# PowerMonitoring.net
KiCad netlist of a schematic drawn in Altium Designer
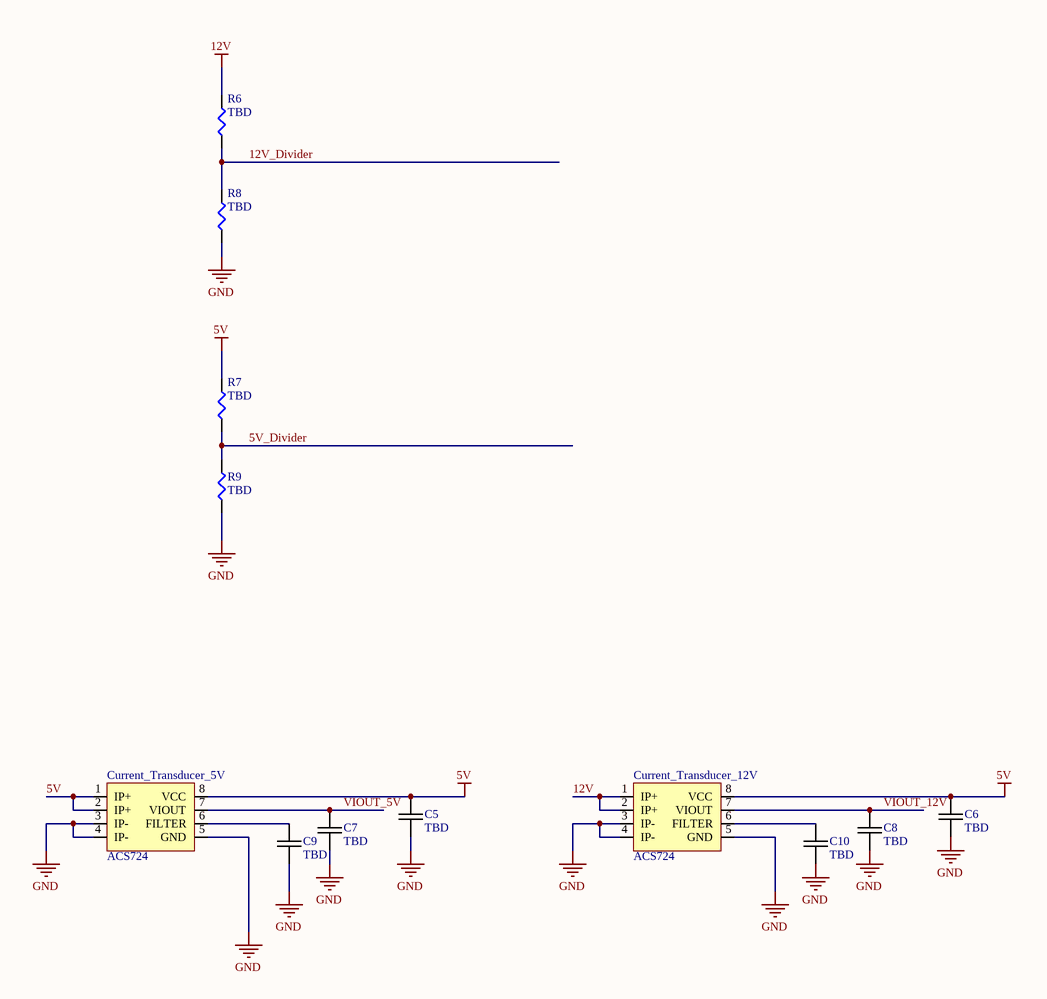
[diagram p0: PowerMonitoring.SchDoc]

(export (version "E")
  (design (tool "Eeschema 10.0.6"))
  (components
    (comp (ref "C5")
      (value "TBD")
      (footprint "0805C-GENERIC")
      (description "CAPACITOR 0805 CERAMIC VALUE TO BE DETERMINED")
      (libsource (lib "MARCS Library Main") (part "0805C-TBD"))
    )
    (comp (ref "C6")
      (value "TBD")
      (footprint "0805C-GENERIC")
      (description "CAPACITOR 0805 CERAMIC VALUE TO BE DETERMINED")
      (libsource (lib "MARCS Library Main") (part "0805C-TBD"))
    )
    (comp (ref "C7")
      (value "TBD")
      (footprint "0805C-GENERIC")
      (description "CAPACITOR 0805 CERAMIC VALUE TO BE DETERMINED")
      (libsource (lib "MARCS Library Main") (part "0805C-TBD"))
    )
    (comp (ref "C8")
      (value "TBD")
      (footprint "0805C-GENERIC")
      (description "CAPACITOR 0805 CERAMIC VALUE TO BE DETERMINED")
      (libsource (lib "MARCS Library Main") (part "0805C-TBD"))
    )
    (comp (ref "C9")
      (value "TBD")
      (footprint "0805C-GENERIC")
      (description "CAPACITOR 0805 CERAMIC VALUE TO BE DETERMINED")
      (libsource (lib "MARCS Library Main") (part "0805C-TBD"))
    )
    (comp (ref "C10")
      (value "TBD")
      (footprint "0805C-GENERIC")
      (description "CAPACITOR 0805 CERAMIC VALUE TO BE DETERMINED")
      (libsource (lib "MARCS Library Main") (part "0805C-TBD"))
    )
    (comp (ref "Current_Transducer_5V")
      (value "ACS724")
      (footprint "SOIC-8 V3")
      (libsource (lib "MARCS Library Main") (part "ACS724"))
    )
    (comp (ref "Current_Transducer_12V")
      (value "ACS724")
      (footprint "SOIC-8 V3")
      (libsource (lib "MARCS Library Main") (part "ACS724"))
    )
    (comp (ref "R6")
      (value "TBD")
      (footprint "0805R-GENERIC")
      (description "RESISTOR 0805 VALUE TO BE DETERMINED")
      (libsource (lib "MARCS Library Main") (part "0805R-TBD"))
    )
    (comp (ref "R7")
      (value "TBD")
      (footprint "0805R-GENERIC")
      (description "RESISTOR 0805 VALUE TO BE DETERMINED")
      (libsource (lib "MARCS Library Main") (part "0805R-TBD"))
    )
    (comp (ref "R8")
      (value "TBD")
      (footprint "0805R-GENERIC")
      (description "RESISTOR 0805 VALUE TO BE DETERMINED")
      (libsource (lib "MARCS Library Main") (part "0805R-TBD"))
    )
    (comp (ref "R9")
      (value "TBD")
      (footprint "0805R-GENERIC")
      (description "RESISTOR 0805 VALUE TO BE DETERMINED")
      (libsource (lib "MARCS Library Main") (part "0805R-TBD"))
    )
  )
  (nets
    (net (code "1") (name "/5V_Divider") (class "Default")
      (node (ref "R7") (pin "1") (pintype "passive"))
      (node (ref "R9") (pin "1") (pintype "passive"))
    )
    (net (code "2") (name "/12V_Divider") (class "Default")
      (node (ref "R6") (pin "1") (pintype "passive"))
      (node (ref "R8") (pin "2") (pintype "passive"))
    )
    (net (code "3") (name "/VIOUT_5V") (class "Default")
      (node (ref "C7") (pin "1") (pintype "passive"))
      (node (ref "Current_Transducer_5V") (pin "7") (pinfunction "VIOUT_7") (pintype "passive"))
    )
    (net (code "4") (name "/VIOUT_12V") (class "Default")
      (node (ref "C8") (pin "1") (pintype "passive"))
      (node (ref "Current_Transducer_12V") (pin "7") (pinfunction "VIOUT_7") (pintype "passive"))
    )
    (net (code "5") (name "5V") (class "Default")
      (node (ref "C5") (pin "1") (pintype "passive"))
      (node (ref "C6") (pin "1") (pintype "passive"))
      (node (ref "Current_Transducer_12V") (pin "8") (pinfunction "VCC_8") (pintype "passive"))
      (node (ref "Current_Transducer_5V") (pin "1") (pinfunction "IP+_1") (pintype "passive"))
      (node (ref "Current_Transducer_5V") (pin "2") (pinfunction "IP+_2") (pintype "passive"))
      (node (ref "Current_Transducer_5V") (pin "8") (pinfunction "VCC_8") (pintype "passive"))
      (node (ref "R7") (pin "2") (pintype "passive"))
    )
    (net (code "6") (name "12V") (class "Default")
      (node (ref "Current_Transducer_12V") (pin "1") (pinfunction "IP+_1") (pintype "passive"))
      (node (ref "Current_Transducer_12V") (pin "2") (pinfunction "IP+_2") (pintype "passive"))
      (node (ref "R6") (pin "2") (pintype "passive"))
    )
    (net (code "7") (name "GND") (class "Default")
      (node (ref "C10") (pin "2") (pintype "passive"))
      (node (ref "C5") (pin "2") (pintype "passive"))
      (node (ref "C6") (pin "2") (pintype "passive"))
      (node (ref "C7") (pin "2") (pintype "passive"))
      (node (ref "C8") (pin "2") (pintype "passive"))
      (node (ref "C9") (pin "2") (pintype "passive"))
      (node (ref "Current_Transducer_12V") (pin "3") (pinfunction "IP-_3") (pintype "passive"))
      (node (ref "Current_Transducer_12V") (pin "4") (pinfunction "IP-_4") (pintype "passive"))
      (node (ref "Current_Transducer_12V") (pin "5") (pinfunction "GND_5") (pintype "passive"))
      (node (ref "Current_Transducer_5V") (pin "3") (pinfunction "IP-_3") (pintype "passive"))
      (node (ref "Current_Transducer_5V") (pin "4") (pinfunction "IP-_4") (pintype "passive"))
      (node (ref "Current_Transducer_5V") (pin "5") (pinfunction "GND_5") (pintype "passive"))
      (node (ref "R8") (pin "1") (pintype "passive"))
      (node (ref "R9") (pin "2") (pintype "passive"))
    )
    (net (code "8") (name "Net-(Current_Transducer_5V-FILTER)") (class "Default")
      (node (ref "C9") (pin "1") (pintype "passive"))
      (node (ref "Current_Transducer_5V") (pin "6") (pinfunction "FILTER_6") (pintype "passive"))
    )
    (net (code "9") (name "Net-(Current_Transducer_12V-FILTER)") (class "Default")
      (node (ref "C10") (pin "1") (pintype "passive"))
      (node (ref "Current_Transducer_12V") (pin "6") (pinfunction "FILTER_6") (pintype "passive"))
    )
  )
)
